# RJ45_1.net
KiCad netlist of a schematic drawn in Altium Designer
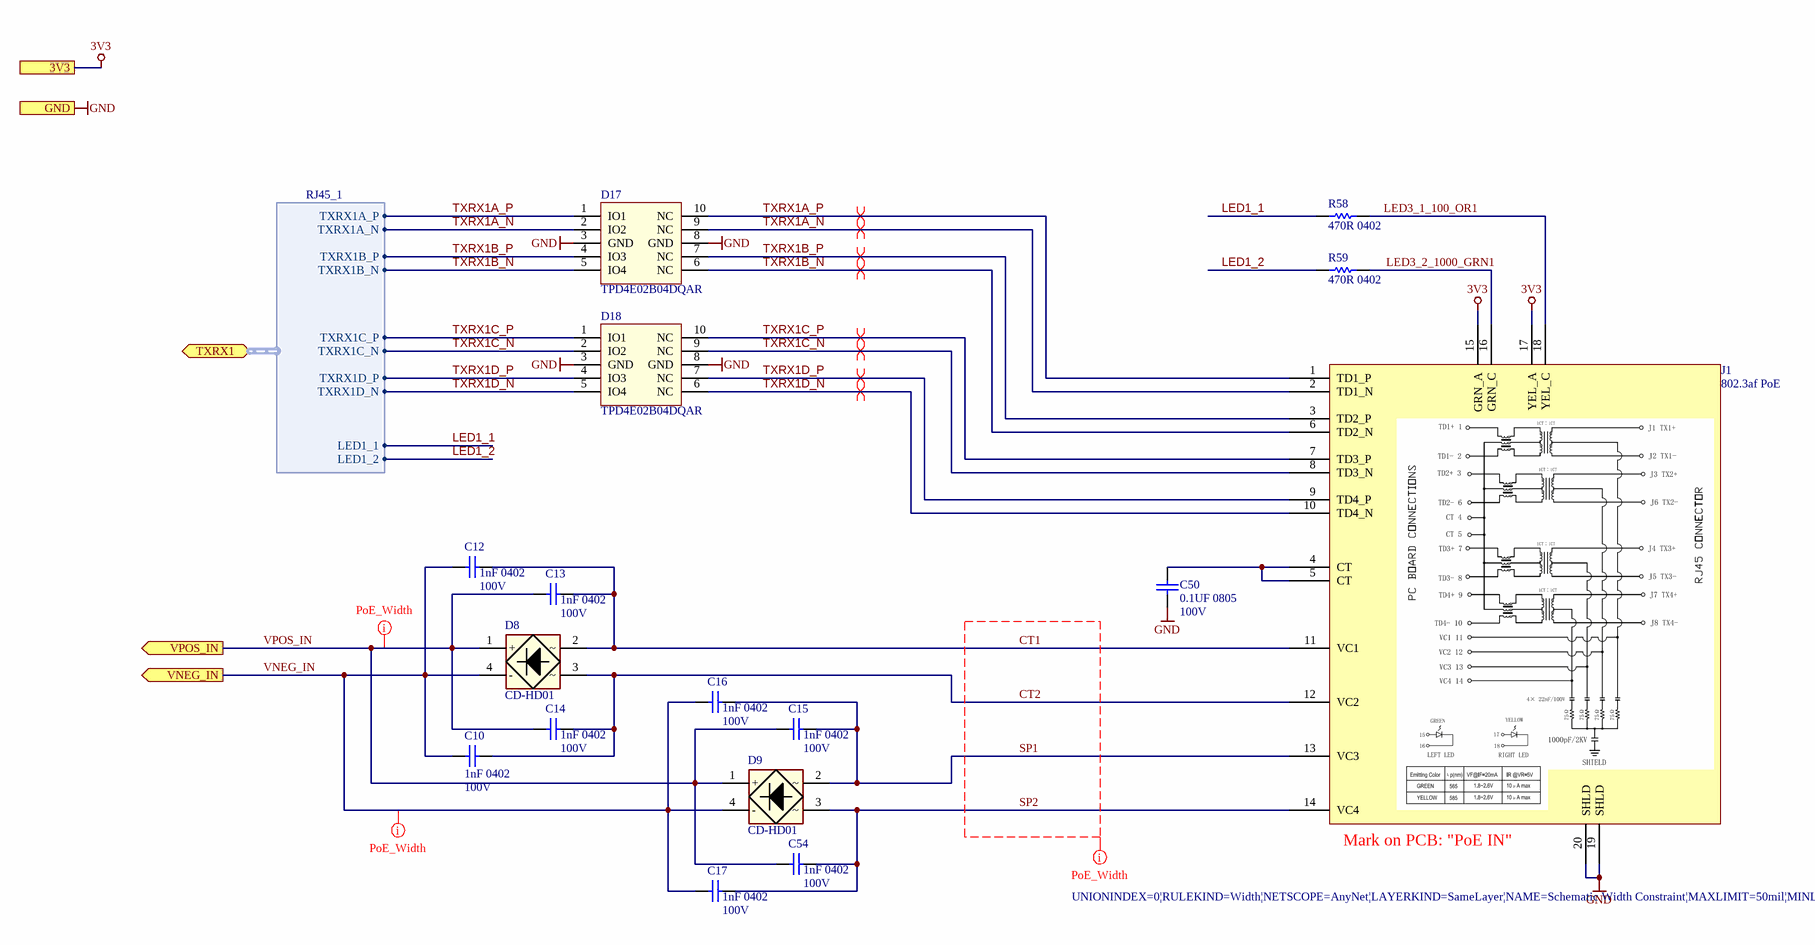
[diagram p0: RJ45_1.SchDoc]

(export (version "E")
  (design (tool "Eeschema 10.0.6"))
  (components
    (comp (ref "C10")
      (value "1nF 0402")
      (footprint "CAP_Altium_Vault_Generic:CAPC0402(1005)60_N")
      (description "CAP CER 1000PF 100V X7R 0402")
      (fields (field (name "TOLERANCE") "10%") (field (name "VOLTAGE") "100V"))
      (libsource (lib "PCBProject") (part "GRM155R72A102KA01D"))
    )
    (comp (ref "C12")
      (value "1nF 0402")
      (footprint "CAP_Altium_Vault_Generic:CAPC0402(1005)60_N")
      (description "CAP CER 1000PF 100V X7R 0402")
      (fields (field (name "TOLERANCE") "10%") (field (name "VOLTAGE") "100V"))
      (libsource (lib "PCBProject") (part "GRM155R72A102KA01D"))
    )
    (comp (ref "C13")
      (value "1nF 0402")
      (footprint "CAP_Altium_Vault_Generic:CAPC0402(1005)60_N")
      (description "CAP CER 1000PF 100V X7R 0402")
      (fields (field (name "TOLERANCE") "10%") (field (name "VOLTAGE") "100V"))
      (libsource (lib "PCBProject") (part "GRM155R72A102KA01D"))
    )
    (comp (ref "C14")
      (value "1nF 0402")
      (footprint "CAP_Altium_Vault_Generic:CAPC0402(1005)60_N")
      (description "CAP CER 1000PF 100V X7R 0402")
      (fields (field (name "TOLERANCE") "10%") (field (name "VOLTAGE") "100V"))
      (libsource (lib "PCBProject") (part "GRM155R72A102KA01D"))
    )
    (comp (ref "C15")
      (value "1nF 0402")
      (footprint "CAP_Altium_Vault_Generic:CAPC0402(1005)60_N")
      (description "CAP CER 1000PF 100V X7R 0402")
      (fields (field (name "TOLERANCE") "10%") (field (name "VOLTAGE") "100V"))
      (libsource (lib "PCBProject") (part "GRM155R72A102KA01D"))
    )
    (comp (ref "C16")
      (value "1nF 0402")
      (footprint "CAP_Altium_Vault_Generic:CAPC0402(1005)60_N")
      (description "CAP CER 1000PF 100V X7R 0402")
      (fields (field (name "TOLERANCE") "10%") (field (name "VOLTAGE") "100V"))
      (libsource (lib "PCBProject") (part "GRM155R72A102KA01D"))
    )
    (comp (ref "C17")
      (value "1nF 0402")
      (footprint "CAP_Altium_Vault_Generic:CAPC0402(1005)60_N")
      (description "CAP CER 1000PF 100V X7R 0402")
      (fields (field (name "TOLERANCE") "10%") (field (name "VOLTAGE") "100V"))
      (libsource (lib "PCBProject") (part "GRM155R72A102KA01D"))
    )
    (comp (ref "C50")
      (value "0.1UF 0805")
      (footprint "CAP_Altium_Vault_Generic:CAPC0805(2012)145_N")
      (description "CAP CER 0.1UF 100V X7R 0805")
      (fields (field (name "TOLERANCE") "10%") (field (name "VOLTAGE RATING") "100V"))
      (libsource (lib "PCBProject") (part "CL21B104KCFNNNE"))
    )
    (comp (ref "C54")
      (value "1nF 0402")
      (footprint "CAP_Altium_Vault_Generic:CAPC0402(1005)60_N")
      (description "CAP CER 1000PF 100V X7R 0402")
      (fields (field (name "TOLERANCE") "10%") (field (name "VOLTAGE") "100V"))
      (libsource (lib "PCBProject") (part "GRM155R72A102KA01D"))
    )
    (comp (ref "D8")
      (value "CD-HD01")
      (footprint "SMD-4")
      (description "CD-HD0x Series Schottky Bridge Rectifier Diode 100V 4-Pin Surface Mount T/R")
      (libsource (lib "BW2098POE_Anfa") (part "CD-HD01"))
    )
    (comp (ref "D9")
      (value "CD-HD01")
      (footprint "SMD-4")
      (description "CD-HD0x Series Schottky Bridge Rectifier Diode 100V 4-Pin Surface Mount T/R")
      (libsource (lib "BW2098POE_Anfa") (part "CD-HD01"))
    )
    (comp (ref "D17")
      (value "TPD4E02B04DQAR")
      (footprint "LuxonisMaster:TPD4E02B04DQAR")
      (libsource (lib "LuxonisMaster") (part "TPD4E02B04DQAR"))
    )
    (comp (ref "D18")
      (value "TPD4E02B04DQAR")
      (footprint "LuxonisMaster:TPD4E02B04DQAR")
      (libsource (lib "LuxonisMaster") (part "TPD4E02B04DQAR"))
    )
    (comp (ref "J1")
      (value "802.3af PoE")
      (footprint "BW2098POE:TRJG0926HENL")
      (description "CONN MAGJACK 1PORT 1000 BASET")
      (libsource (lib "BW2098POE") (part "TRJG0926HENL"))
    )
    (comp (ref "R58")
      (value "470R 0402")
      (footprint "RESC0402(1005)_N")
      (description "RES SMD 470 OHM 1% 1/16W 0402")
      (fields (field (name "TOLERANCE") "1%"))
      (libsource (lib "LuxonisMaster") (part "CRCW0402470RFKED"))
    )
    (comp (ref "R59")
      (value "470R 0402")
      (footprint "RESC0402(1005)_N")
      (description "RES SMD 470 OHM 1% 1/16W 0402")
      (fields (field (name "TOLERANCE") "1%"))
      (libsource (lib "LuxonisMaster") (part "CRCW0402470RFKED"))
    )
  )
  (nets
    (net (code "2") (name "/CT1") (class "Default")
      (node (ref "C12") (pin "1") (pinfunction "1_1") (pintype "passive"))
      (node (ref "C13") (pin "1") (pinfunction "1_1") (pintype "passive"))
      (node (ref "D8") (pin "2") (pinfunction "~_2") (pintype "passive"))
      (node (ref "J1") (pin "11") (pinfunction "VC1_11") (pintype "passive"))
    )
    (net (code "3") (name "/CT2") (class "Default")
      (node (ref "C10") (pin "1") (pinfunction "1_1") (pintype "passive"))
      (node (ref "C14") (pin "1") (pinfunction "1_1") (pintype "passive"))
      (node (ref "D8") (pin "3") (pinfunction "~_3") (pintype "passive"))
      (node (ref "J1") (pin "12") (pinfunction "VC2_12") (pintype "passive"))
    )
    (net (code "4") (name "/LED1_1") (class "Default")
      (node (ref "R58") (pin "1") (pinfunction "1_1") (pintype "passive"))
    )
    (net (code "5") (name "/LED1_2") (class "Default")
      (node (ref "R59") (pin "1") (pinfunction "1_1") (pintype "passive"))
    )
    (net (code "6") (name "/LED3_1_100_OR1") (class "Default")
      (node (ref "J1") (pin "18") (pinfunction "YEL_C_18") (pintype "passive"))
      (node (ref "R58") (pin "2") (pinfunction "2_2") (pintype "passive"))
    )
    (net (code "7") (name "/LED3_2_1000_GRN1") (class "Default")
      (node (ref "J1") (pin "16") (pinfunction "GRN_C_16") (pintype "passive"))
      (node (ref "R59") (pin "2") (pinfunction "2_2") (pintype "passive"))
    )
    (net (code "8") (name "/SP1") (class "Default")
      (node (ref "C15") (pin "1") (pinfunction "1_1") (pintype "passive"))
      (node (ref "C16") (pin "1") (pinfunction "1_1") (pintype "passive"))
      (node (ref "D9") (pin "2") (pinfunction "~_2") (pintype "passive"))
      (node (ref "J1") (pin "13") (pinfunction "VC3_13") (pintype "passive"))
    )
    (net (code "9") (name "/SP2") (class "Default")
      (node (ref "C17") (pin "1") (pinfunction "1_1") (pintype "passive"))
      (node (ref "C54") (pin "1") (pinfunction "1_1") (pintype "passive"))
      (node (ref "D9") (pin "3") (pinfunction "~_3") (pintype "passive"))
      (node (ref "J1") (pin "14") (pinfunction "VC4_14") (pintype "passive"))
    )
    (net (code "10") (name "/TXRX1A_N") (class "Default")
      (node (ref "D17") (pin "2") (pinfunction "IO2_2") (pintype "passive"))
      (node (ref "D17") (pin "9") (pinfunction "NC_9") (pintype "passive"))
      (node (ref "J1") (pin "2") (pinfunction "TD1_N_2") (pintype "passive"))
    )
    (net (code "11") (name "/TXRX1A_P") (class "Default")
      (node (ref "D17") (pin "1") (pinfunction "IO1_1") (pintype "passive"))
      (node (ref "D17") (pin "10") (pinfunction "NC_10") (pintype "passive"))
      (node (ref "J1") (pin "1") (pinfunction "TD1_P_1") (pintype "passive"))
    )
    (net (code "12") (name "/TXRX1B_N") (class "Default")
      (node (ref "D17") (pin "5") (pinfunction "IO4_5") (pintype "passive"))
      (node (ref "D17") (pin "6") (pinfunction "NC_6") (pintype "passive"))
      (node (ref "J1") (pin "6") (pinfunction "TD2_N_6") (pintype "passive"))
    )
    (net (code "13") (name "/TXRX1B_P") (class "Default")
      (node (ref "D17") (pin "4") (pinfunction "IO3_4") (pintype "passive"))
      (node (ref "D17") (pin "7") (pinfunction "NC_7") (pintype "passive"))
      (node (ref "J1") (pin "3") (pinfunction "TD2_P_3") (pintype "passive"))
    )
    (net (code "14") (name "/TXRX1C_N") (class "Default")
      (node (ref "D18") (pin "2") (pinfunction "IO2_2") (pintype "passive"))
      (node (ref "D18") (pin "9") (pinfunction "NC_9") (pintype "passive"))
      (node (ref "J1") (pin "8") (pinfunction "TD3_N_8") (pintype "passive"))
    )
    (net (code "15") (name "/TXRX1C_P") (class "Default")
      (node (ref "D18") (pin "1") (pinfunction "IO1_1") (pintype "passive"))
      (node (ref "D18") (pin "10") (pinfunction "NC_10") (pintype "passive"))
      (node (ref "J1") (pin "7") (pinfunction "TD3_P_7") (pintype "passive"))
    )
    (net (code "16") (name "/TXRX1D_N") (class "Default")
      (node (ref "D18") (pin "5") (pinfunction "IO4_5") (pintype "passive"))
      (node (ref "D18") (pin "6") (pinfunction "NC_6") (pintype "passive"))
      (node (ref "J1") (pin "10") (pinfunction "TD4_N_10") (pintype "passive"))
    )
    (net (code "17") (name "/TXRX1D_P") (class "Default")
      (node (ref "D18") (pin "4") (pinfunction "IO3_4") (pintype "passive"))
      (node (ref "D18") (pin "7") (pinfunction "NC_7") (pintype "passive"))
      (node (ref "J1") (pin "9") (pinfunction "TD4_P_9") (pintype "passive"))
    )
    (net (code "18") (name "/VNEG_IN") (class "Default")
      (node (ref "C10") (pin "2") (pinfunction "2_2") (pintype "passive"))
      (node (ref "C12") (pin "2") (pinfunction "2_2") (pintype "passive"))
      (node (ref "C16") (pin "2") (pinfunction "2_2") (pintype "passive"))
      (node (ref "C17") (pin "2") (pinfunction "2_2") (pintype "passive"))
      (node (ref "D8") (pin "4") (pinfunction "-_4") (pintype "passive"))
      (node (ref "D9") (pin "4") (pinfunction "-_4") (pintype "passive"))
    )
    (net (code "19") (name "/VPOS_IN") (class "Default")
      (node (ref "C13") (pin "2") (pinfunction "2_2") (pintype "passive"))
      (node (ref "C14") (pin "2") (pinfunction "2_2") (pintype "passive"))
      (node (ref "C15") (pin "2") (pinfunction "2_2") (pintype "passive"))
      (node (ref "C54") (pin "2") (pinfunction "2_2") (pintype "passive"))
      (node (ref "D8") (pin "1") (pinfunction "+_1") (pintype "passive"))
      (node (ref "D9") (pin "1") (pinfunction "+_1") (pintype "passive"))
    )
    (net (code "21") (name "3V3") (class "Default")
      (node (ref "J1") (pin "15") (pinfunction "GRN_A_15") (pintype "passive"))
      (node (ref "J1") (pin "17") (pinfunction "YEL_A_17") (pintype "passive"))
    )
    (net (code "22") (name "GND") (class "Default")
      (node (ref "C50") (pin "1") (pinfunction "1_1") (pintype "passive"))
      (node (ref "D17") (pin "3") (pinfunction "GND_3") (pintype "passive"))
      (node (ref "D17") (pin "8") (pinfunction "GND_8") (pintype "passive"))
      (node (ref "D18") (pin "3") (pinfunction "GND_3") (pintype "passive"))
      (node (ref "D18") (pin "8") (pinfunction "GND_8") (pintype "passive"))
      (node (ref "J1") (pin "19") (pinfunction "SHLD_19") (pintype "passive"))
      (node (ref "J1") (pin "20") (pinfunction "SHLD_20") (pintype "passive"))
    )
    (net (code "23") (name "Net-(C50-Pad2)") (class "Default")
      (node (ref "C50") (pin "2") (pinfunction "2_2") (pintype "passive"))
      (node (ref "J1") (pin "4") (pinfunction "CT_4") (pintype "passive"))
      (node (ref "J1") (pin "5") (pinfunction "CT_5") (pintype "passive"))
    )
  )
)
